# Sheet6.net
KiCad netlist of a schematic drawn in Altium Designer
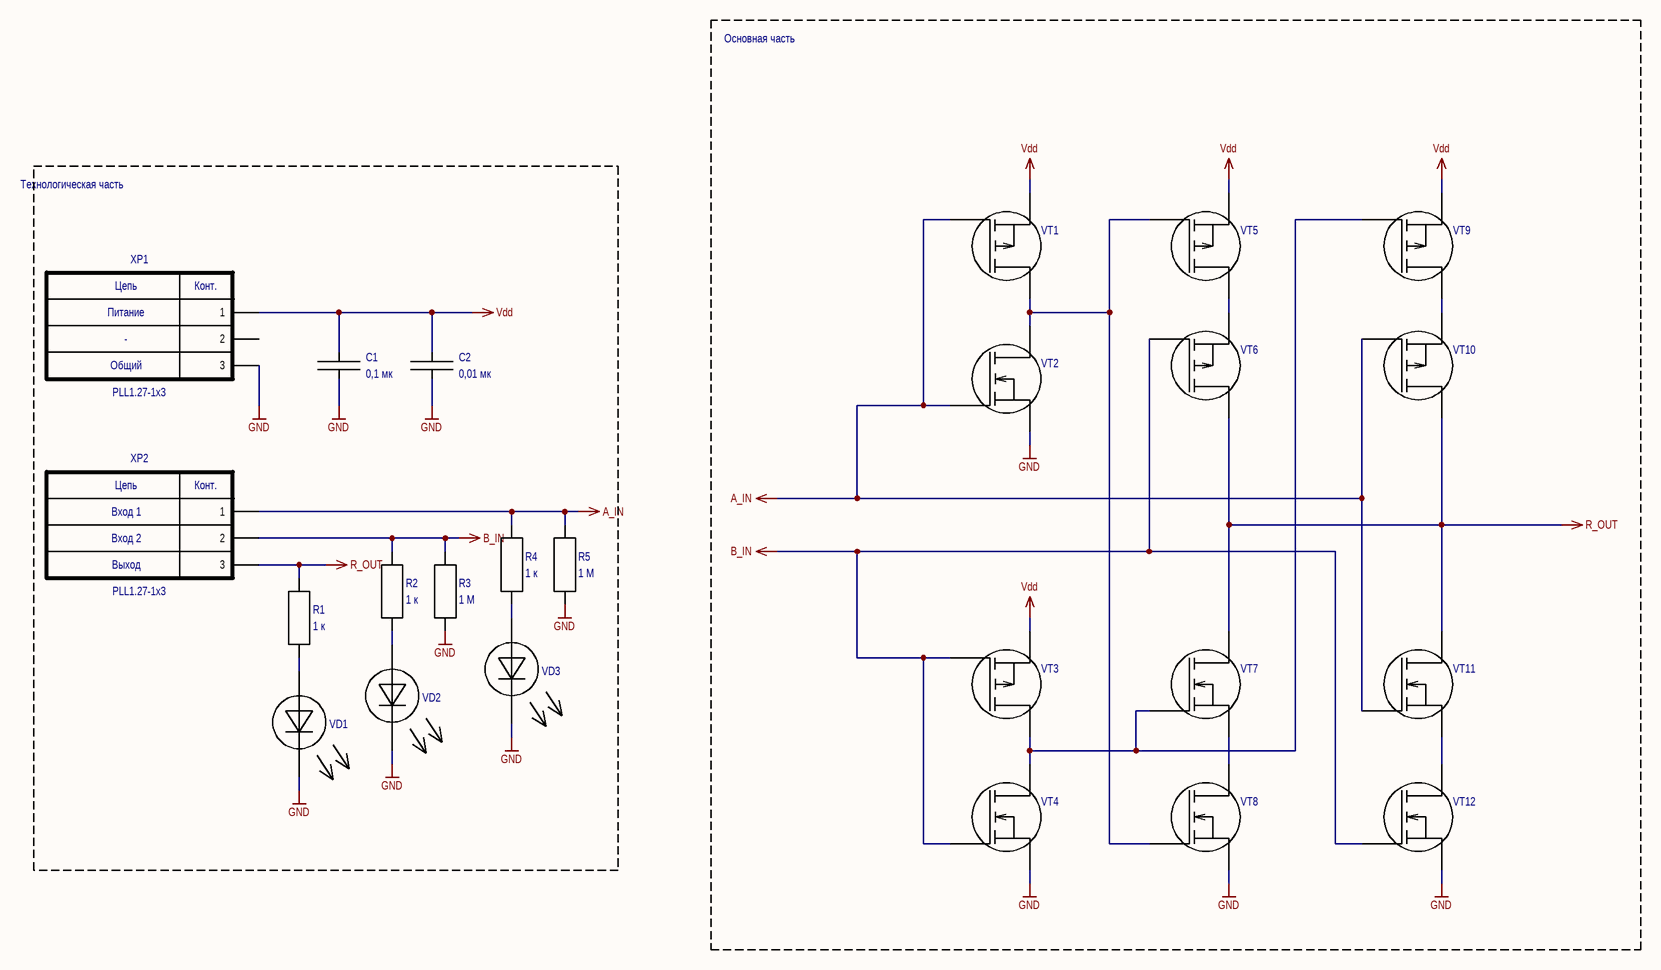
[diagram p0: Sheet6.SchDoc]

(export (version "E")
  (design (tool "Eeschema 10.0.6"))
  (components
    (comp (ref "C1")
      (value "0,1 мк")
      (footprint "XOR:K10-79_1.6_0.8(0603)")
      (fields (field (name "Comment") "0,1 мкФ ±* * * *, *"))
      (libsource (lib "IVT_LIB") (part "C - Конденсатор"))
    )
    (comp (ref "C2")
      (value "0,01 мк")
      (footprint "XOR:K10-79_1.6_0.8(0603)")
      (fields (field (name "Comment") "0,01 мкФ ±* * * *, *"))
      (libsource (lib "IVT_LIB") (part "C - Конденсатор"))
    )
    (comp (ref "R1")
      (value "1 к")
      (footprint "XOR:P1-12-0.1(0603)")
      (fields
        (field (name "PARTNUMBER") "RC0603JR-071KL")
        (field (name "TOLERANCE") "5 %")
        (field (name "Comment") "1 кОм ±5 % 0603, RC0603JR-071KL")
      )
      (libsource (lib "IVT_LIB") (part "R - Резистор"))
    )
    (comp (ref "R2")
      (value "1 к")
      (footprint "XOR:P1-12-0.1(0603)")
      (fields
        (field (name "PARTNUMBER") "RC0603JR-071KL")
        (field (name "TOLERANCE") "5 %")
        (field (name "Comment") "1 кОм ±5 % 0603, RC0603JR-071KL")
      )
      (libsource (lib "IVT_LIB") (part "R - Резистор"))
    )
    (comp (ref "R3")
      (value "1 М")
      (footprint "XOR:P1-12-0.1(0603)")
      (fields
        (field (name "PARTNUMBER") "RC0603JR-071KL")
        (field (name "TOLERANCE") "5 %")
        (field (name "Comment") "1 МОм ±5 % 0603, RC0603JR-071KL")
      )
      (libsource (lib "IVT_LIB") (part "R - Резистор"))
    )
    (comp (ref "R4")
      (value "1 к")
      (footprint "XOR:P1-12-0.1(0603)")
      (fields
        (field (name "PARTNUMBER") "RC0603JR-071KL")
        (field (name "TOLERANCE") "5 %")
        (field (name "Comment") "1 кОм ±5 % 0603, RC0603JR-071KL")
      )
      (libsource (lib "IVT_LIB") (part "R - Резистор"))
    )
    (comp (ref "R5")
      (value "1 М")
      (footprint "XOR:P1-12-0.1(0603)")
      (fields
        (field (name "PARTNUMBER") "RC0603JR-071KL")
        (field (name "TOLERANCE") "5 %")
        (field (name "Comment") "1 МОм ±5 % 0603, RC0603JR-071KL")
      )
      (libsource (lib "IVT_LIB") (part "R - Резистор"))
    )
    (comp (ref "VD1")
      (value "VD - Светодиод")
      (footprint "XOR:LED 0603")
      (fields (field (name "PARTNUMBER") "GNL-0805UBC-TL"))
      (libsource (lib "IVT_LIB") (part "VD - Светодиод"))
    )
    (comp (ref "VD2")
      (value "VD - Светодиод")
      (footprint "XOR:LED 0603")
      (fields (field (name "PARTNUMBER") "GNL-0805UBC-TL"))
      (libsource (lib "IVT_LIB") (part "VD - Светодиод"))
    )
    (comp (ref "VD3")
      (value "VD - Светодиод")
      (footprint "XOR:LED 0603")
      (fields (field (name "PARTNUMBER") "GNL-0805UBC-TL"))
      (libsource (lib "IVT_LIB") (part "VD - Светодиод"))
    )
    (comp (ref "VT1")
      (value "VT - Полевой транзистор P канал (MOSFET_P)")
      (footprint "SOT23(KT-46)")
      (description "VT")
      (libsource (lib "ALU") (part "VT - Полевой транзистор P канал (MOSFET_P)"))
    )
    (comp (ref "VT2")
      (value "VT - Полевой транзистор N канал (MOSFET_N)")
      (footprint "SOT23(KT-46)")
      (description "VT")
      (libsource (lib "ALU") (part "VT - Полевой транзистор N канал (MOSFET_N)"))
    )
    (comp (ref "VT3")
      (value "VT - Полевой транзистор P канал (MOSFET_P)")
      (footprint "SOT23(KT-46)")
      (description "VT")
      (libsource (lib "ALU") (part "VT - Полевой транзистор P канал (MOSFET_P)"))
    )
    (comp (ref "VT4")
      (value "VT - Полевой транзистор N канал (MOSFET_N)")
      (footprint "SOT23(KT-46)")
      (description "VT")
      (libsource (lib "ALU") (part "VT - Полевой транзистор N канал (MOSFET_N)"))
    )
    (comp (ref "VT5")
      (value "VT - Полевой транзистор P канал (MOSFET_P)")
      (footprint "SOT23(KT-46)")
      (description "VT")
      (libsource (lib "ALU") (part "VT - Полевой транзистор P канал (MOSFET_P)"))
    )
    (comp (ref "VT6")
      (value "VT - Полевой транзистор P канал (MOSFET_P)")
      (footprint "SOT23(KT-46)")
      (description "VT")
      (libsource (lib "ALU") (part "VT - Полевой транзистор P канал (MOSFET_P)"))
    )
    (comp (ref "VT7")
      (value "VT - Полевой транзистор N канал (MOSFET_N)")
      (footprint "SOT23(KT-46)")
      (description "VT")
      (libsource (lib "ALU") (part "VT - Полевой транзистор N канал (MOSFET_N)"))
    )
    (comp (ref "VT8")
      (value "VT - Полевой транзистор N канал (MOSFET_N)")
      (footprint "SOT23(KT-46)")
      (description "VT")
      (libsource (lib "ALU") (part "VT - Полевой транзистор N канал (MOSFET_N)"))
    )
    (comp (ref "VT9")
      (value "VT - Полевой транзистор P канал (MOSFET_P)")
      (footprint "SOT23(KT-46)")
      (description "VT")
      (libsource (lib "ALU") (part "VT - Полевой транзистор P канал (MOSFET_P)"))
    )
    (comp (ref "VT10")
      (value "VT - Полевой транзистор P канал (MOSFET_P)")
      (footprint "SOT23(KT-46)")
      (description "VT")
      (libsource (lib "ALU") (part "VT - Полевой транзистор P канал (MOSFET_P)"))
    )
    (comp (ref "VT11")
      (value "VT - Полевой транзистор N канал (MOSFET_N)")
      (footprint "SOT23(KT-46)")
      (description "VT")
      (libsource (lib "ALU") (part "VT - Полевой транзистор N канал (MOSFET_N)"))
    )
    (comp (ref "VT12")
      (value "VT - Полевой транзистор N канал (MOSFET_N)")
      (footprint "SOT23(KT-46)")
      (description "VT")
      (libsource (lib "ALU") (part "VT - Полевой транзистор N канал (MOSFET_N)"))
    )
    (comp (ref "XP1")
      (value "Вилка PLL1.27-1x3 RUICHI")
      (footprint "PCBComponent_1 - duplicate")
      (fields
        (field (name "1") "Питание")
        (field (name "3") "Общий")
        (field (name "2") "-")
        (field (name "PARTNUMBER") "PLL1.27-1x3")
      )
      (libsource (lib "IVT_LIB") (part "X - Контактное поле х3"))
    )
    (comp (ref "XP2")
      (value "KONT_POLE_POWER")
      (footprint "XOR:PCBComponent_1 - duplicate")
      (fields
        (field (name "1") "Вход 1")
        (field (name "2") "Вход 2")
        (field (name "3") "Выход")
        (field (name "PARTNUMBER") "PLL1.27-1x3")
      )
      (libsource (lib "IVT_LIB") (part "X - Контактное поле х3"))
    )
  )
  (nets
    (net (code "1") (name "A_IN") (class "Default")
      (node (ref "R4") (pin "1") (pinfunction "1_1") (pintype "passive"))
      (node (ref "R5") (pin "1") (pinfunction "1_1") (pintype "passive"))
      (node (ref "VT1") (pin "3") (pintype "passive"))
      (node (ref "VT10") (pin "3") (pintype "passive"))
      (node (ref "VT11") (pin "3") (pintype "passive"))
      (node (ref "VT2") (pin "3") (pintype "passive"))
      (node (ref "XP2") (pin "1") (pinfunction "1_1") (pintype "passive"))
    )
    (net (code "2") (name "B_IN") (class "Default")
      (node (ref "R2") (pin "1") (pinfunction "1_1") (pintype "passive"))
      (node (ref "R3") (pin "1") (pinfunction "1_1") (pintype "passive"))
      (node (ref "VT12") (pin "3") (pintype "passive"))
      (node (ref "VT3") (pin "3") (pintype "passive"))
      (node (ref "VT4") (pin "3") (pintype "passive"))
      (node (ref "VT6") (pin "3") (pintype "passive"))
      (node (ref "XP2") (pin "2") (pinfunction "2_2") (pintype "passive"))
    )
    (net (code "3") (name "GND") (class "Default")
      (node (ref "C1") (pin "1") (pinfunction "1_1") (pintype "passive"))
      (node (ref "C2") (pin "1") (pinfunction "1_1") (pintype "passive"))
      (node (ref "R3") (pin "2") (pinfunction "2_2") (pintype "passive"))
      (node (ref "R5") (pin "2") (pinfunction "2_2") (pintype "passive"))
      (node (ref "VD1") (pin "2") (pinfunction "C_2") (pintype "passive"))
      (node (ref "VD2") (pin "2") (pinfunction "C_2") (pintype "passive"))
      (node (ref "VD3") (pin "2") (pinfunction "C_2") (pintype "passive"))
      (node (ref "VT12") (pin "2") (pintype "passive"))
      (node (ref "VT2") (pin "2") (pintype "passive"))
      (node (ref "VT4") (pin "2") (pintype "passive"))
      (node (ref "VT8") (pin "2") (pintype "passive"))
      (node (ref "XP1") (pin "3") (pinfunction "3_3") (pintype "passive"))
    )
    (net (code "4") (name "Net-(VD1-A)") (class "Default")
      (node (ref "R1") (pin "2") (pinfunction "2_2") (pintype "passive"))
      (node (ref "VD1") (pin "1") (pinfunction "A_1") (pintype "passive"))
    )
    (net (code "5") (name "Net-(VD2-A)") (class "Default")
      (node (ref "R2") (pin "2") (pinfunction "2_2") (pintype "passive"))
      (node (ref "VD2") (pin "1") (pinfunction "A_1") (pintype "passive"))
    )
    (net (code "6") (name "Net-(VD3-A)") (class "Default")
      (node (ref "R4") (pin "2") (pinfunction "2_2") (pintype "passive"))
      (node (ref "VD3") (pin "1") (pinfunction "A_1") (pintype "passive"))
    )
    (net (code "7") (name "Net-(VT1-Pad2)") (class "Default")
      (node (ref "VT1") (pin "2") (pintype "passive"))
      (node (ref "VT2") (pin "1") (pintype "passive"))
      (node (ref "VT5") (pin "3") (pintype "passive"))
      (node (ref "VT8") (pin "3") (pintype "passive"))
    )
    (net (code "8") (name "Net-(VT3-Pad2)") (class "Default")
      (node (ref "VT3") (pin "2") (pintype "passive"))
      (node (ref "VT4") (pin "1") (pintype "passive"))
      (node (ref "VT7") (pin "3") (pintype "passive"))
      (node (ref "VT9") (pin "3") (pintype "passive"))
    )
    (net (code "9") (name "Net-(VT5-Pad2)") (class "Default")
      (node (ref "VT5") (pin "2") (pintype "passive"))
      (node (ref "VT6") (pin "1") (pintype "passive"))
    )
    (net (code "10") (name "Net-(VT7-Pad2)") (class "Default")
      (node (ref "VT7") (pin "2") (pintype "passive"))
      (node (ref "VT8") (pin "1") (pintype "passive"))
    )
    (net (code "11") (name "Net-(VT10-Pad1)") (class "Default")
      (node (ref "VT10") (pin "1") (pintype "passive"))
      (node (ref "VT9") (pin "2") (pintype "passive"))
    )
    (net (code "12") (name "Net-(VT11-Pad2)") (class "Default")
      (node (ref "VT11") (pin "2") (pintype "passive"))
      (node (ref "VT12") (pin "1") (pintype "passive"))
    )
    (net (code "13") (name "R_OUT") (class "Default")
      (node (ref "R1") (pin "1") (pinfunction "1_1") (pintype "passive"))
      (node (ref "VT10") (pin "2") (pintype "passive"))
      (node (ref "VT11") (pin "1") (pintype "passive"))
      (node (ref "VT6") (pin "2") (pintype "passive"))
      (node (ref "VT7") (pin "1") (pintype "passive"))
      (node (ref "XP2") (pin "3") (pinfunction "3_3") (pintype "passive"))
    )
    (net (code "14") (name "Vdd") (class "Default")
      (node (ref "C1") (pin "2") (pinfunction "2_2") (pintype "passive"))
      (node (ref "C2") (pin "2") (pinfunction "2_2") (pintype "passive"))
      (node (ref "VT1") (pin "1") (pintype "passive"))
      (node (ref "VT3") (pin "1") (pintype "passive"))
      (node (ref "VT5") (pin "1") (pintype "passive"))
      (node (ref "VT9") (pin "1") (pintype "passive"))
      (node (ref "XP1") (pin "1") (pinfunction "1_1") (pintype "passive"))
    )
    (net (code "15") (name "unconnected-(XP1-Pad2)") (class "Default")
      (node (ref "XP1") (pin "2") (pinfunction "2_2") (pintype "passive"))
    )
  )
)
